# uc4h_gpsmagbaro_ws2812_v0100.net
KiCad netlist of a schematic drawn in EAGLE
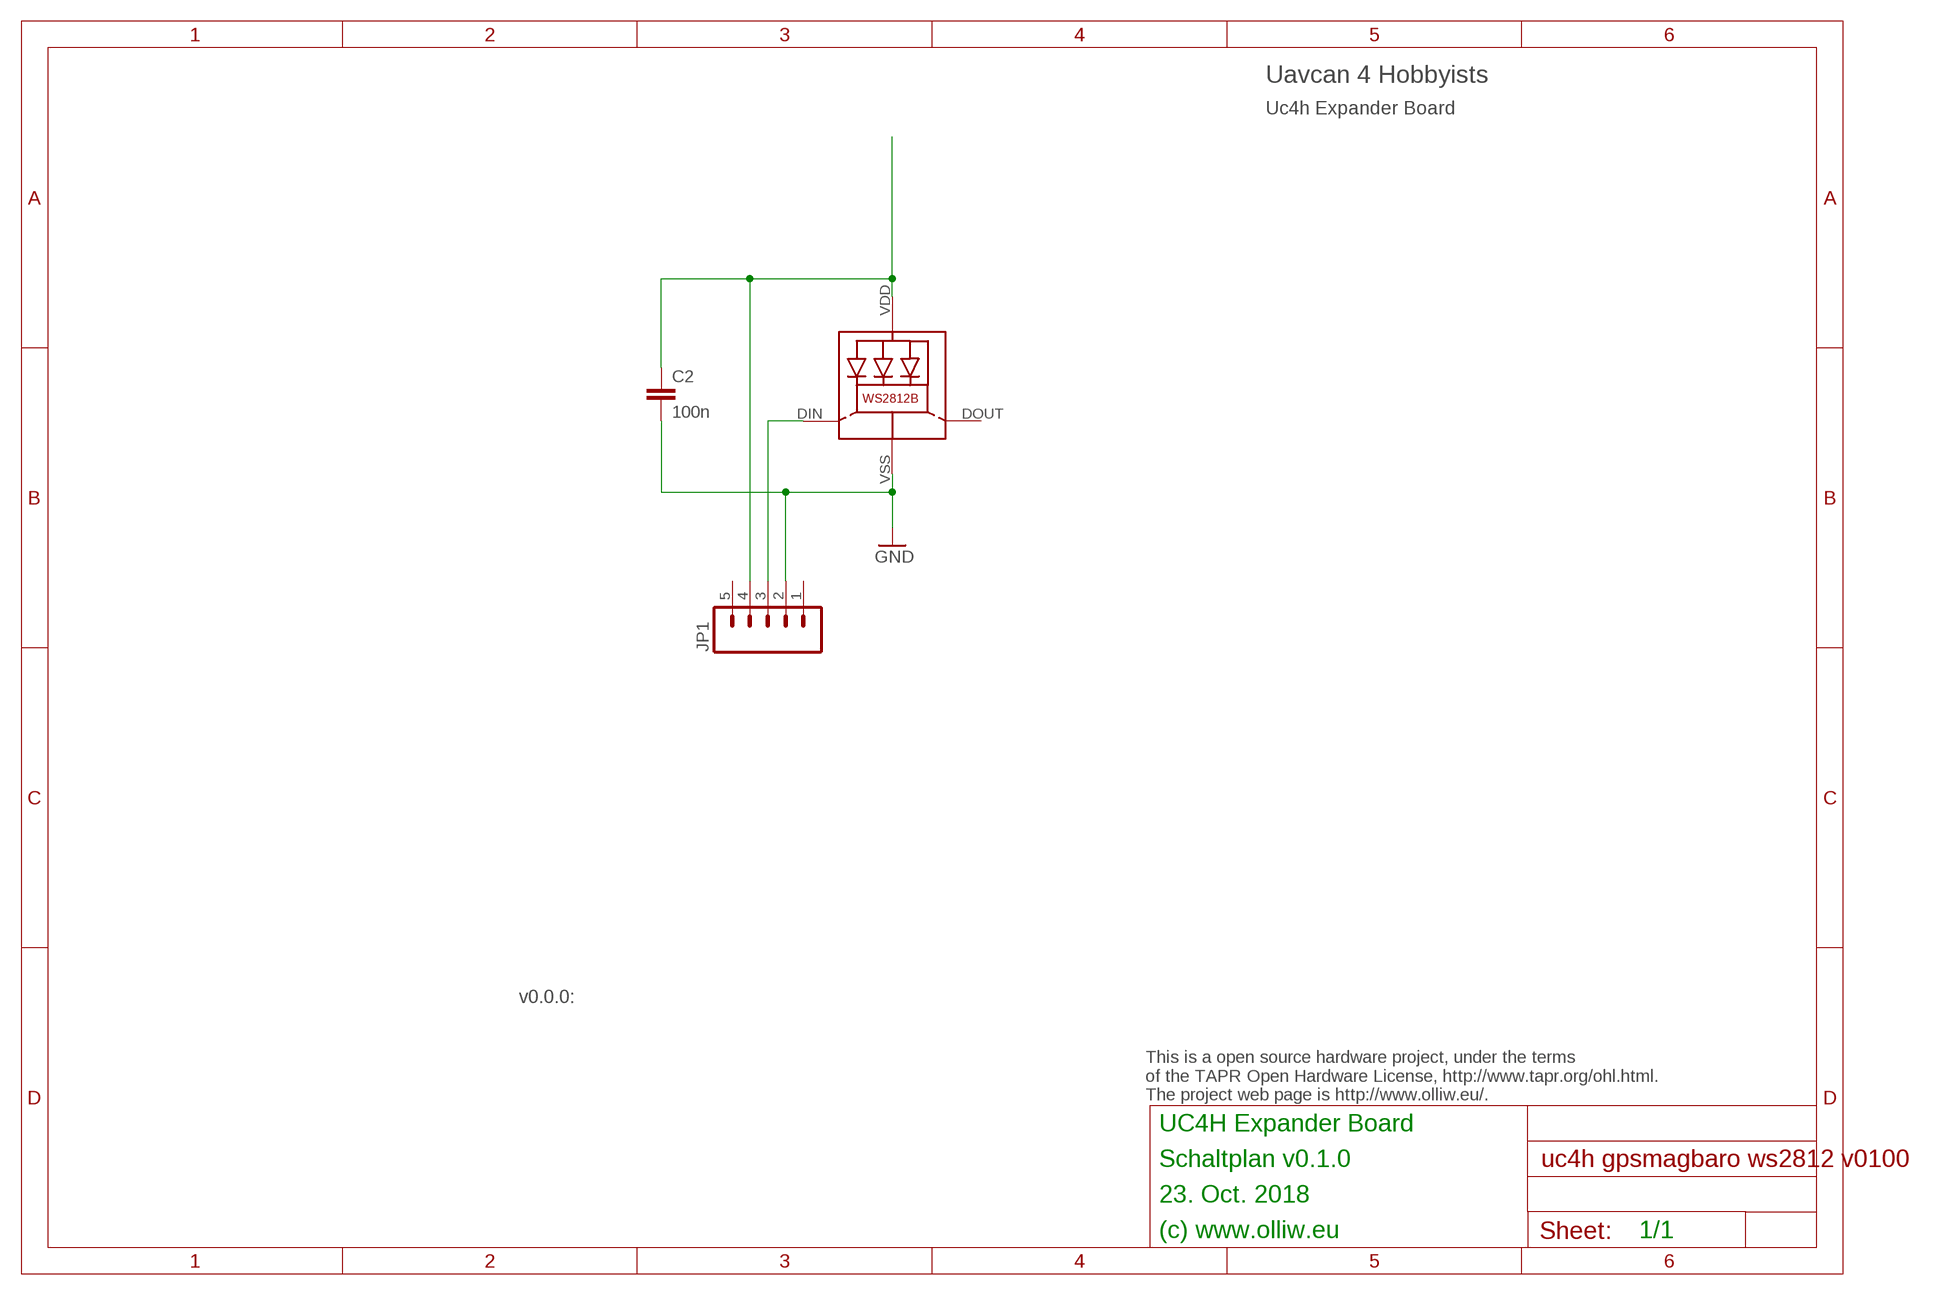
[diagram p0: schematic, sheet 1]

(export (version "E")
  (design (tool "Eeschema 10.0.6"))
  (components
    (comp (ref "C2")
      (value "100n")
      (footprint "eagle-import:C0402")
      (libsource (lib "eagle-import") (part "C-EUC0402"))
    )
    (comp (ref "JP1")
      (value "M05PTH")
      (footprint "eagle-import:1X05")
      (libsource (lib "eagle-import") (part "M05PTH"))
    )
    (comp (ref "LED1")
      (value "WS2812B")
      (footprint "eagle-import:WS2812B")
      (libsource (lib "eagle-import") (part "WS2812B"))
    )
  )
  (nets
    (net (code "1") (name "GND") (class "Default")
      (node (ref "C2") (pin "2") (pinfunction "2_2") (pintype "passive"))
      (node (ref "JP1") (pin "2") (pinfunction "2_2") (pintype "passive"))
      (node (ref "LED1") (pin "VSS") (pinfunction "GND_VSS") (pintype "power_in"))
    )
    (net (code "2") (name "Net-(C2-Pad1)") (class "Default")
      (node (ref "C2") (pin "1") (pinfunction "1_1") (pintype "passive"))
      (node (ref "JP1") (pin "4") (pinfunction "4_4") (pintype "passive"))
      (node (ref "LED1") (pin "VDD") (pinfunction "VDD_VDD") (pintype "power_in"))
    )
    (net (code "3") (name "Net-(LED1-DI)") (class "Default")
      (node (ref "JP1") (pin "3") (pinfunction "3_3") (pintype "passive"))
      (node (ref "LED1") (pin "DIN") (pinfunction "DI_DIN") (pintype "input"))
    )
    (net (code "4") (name "unconnected-(JP1-Pad1)") (class "Default")
      (node (ref "JP1") (pin "1") (pinfunction "1_1") (pintype "passive"))
    )
    (net (code "5") (name "unconnected-(JP1-Pad5)") (class "Default")
      (node (ref "JP1") (pin "5") (pinfunction "5_5") (pintype "passive"))
    )
    (net (code "6") (name "unconnected-(LED1-DO-PadDOUT)") (class "Default")
      (node (ref "LED1") (pin "DOUT") (pinfunction "DO_DOUT") (pintype "output"))
    )
  )
)
